# PDM_ROCKPIS_PoE_HAT_FPC.net
KiCad netlist of a schematic drawn in Altium Designer
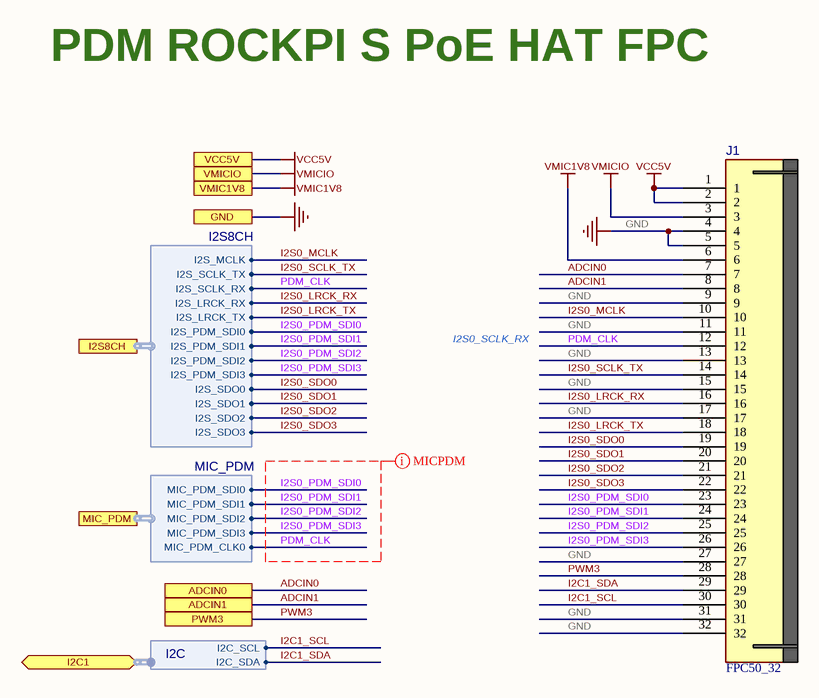
[diagram p0: PDM_ROCKPIS_PoE_HAT_FPC.SchDoc]

(export (version "E")
  (design (tool "Eeschema 10.0.6"))
  (components
    (comp (ref "J1")
      (value "FPC50_32")
      (footprint "FPC50_32D")
      (description "CONN, FPC, 0.50mm pitch, RightAngle, Bot. Contact")
      (fields (field (name "MANF") "OMRON") (field (name "MANF_P#") "XF2M-3215-1A"))
      (libsource (lib "conn_fpc") (part "FPC50_32D"))
    )
  )
  (nets
    (net (code "4") (name "/ADCIN0") (class "Default")
      (node (ref "J1") (pin "7") (pinfunction "7_7") (pintype "passive"))
    )
    (net (code "5") (name "/ADCIN1") (class "Default")
      (node (ref "J1") (pin "8") (pinfunction "8_8") (pintype "passive"))
    )
    (net (code "6") (name "/I2C1_SCL") (class "Default")
      (node (ref "J1") (pin "30") (pinfunction "30_30") (pintype "passive"))
    )
    (net (code "7") (name "/I2C1_SDA") (class "Default")
      (node (ref "J1") (pin "29") (pinfunction "29_29") (pintype "passive"))
    )
    (net (code "8") (name "/I2S0_LRCK_RX") (class "Default")
      (node (ref "J1") (pin "16") (pinfunction "16_16") (pintype "passive"))
    )
    (net (code "9") (name "/I2S0_LRCK_TX") (class "Default")
      (node (ref "J1") (pin "18") (pinfunction "18_18") (pintype "passive"))
    )
    (net (code "10") (name "/I2S0_MCLK") (class "Default")
      (node (ref "J1") (pin "10") (pinfunction "10_10") (pintype "passive"))
    )
    (net (code "11") (name "/I2S0_PDM_SDI0") (class "Default")
      (node (ref "J1") (pin "23") (pinfunction "23_23") (pintype "passive"))
    )
    (net (code "12") (name "/I2S0_PDM_SDI1") (class "Default")
      (node (ref "J1") (pin "24") (pinfunction "24_24") (pintype "passive"))
    )
    (net (code "13") (name "/I2S0_PDM_SDI2") (class "Default")
      (node (ref "J1") (pin "25") (pinfunction "25_25") (pintype "passive"))
    )
    (net (code "14") (name "/I2S0_PDM_SDI3") (class "Default")
      (node (ref "J1") (pin "26") (pinfunction "26_26") (pintype "passive"))
    )
    (net (code "15") (name "/I2S0_SCLK_TX") (class "Default")
      (node (ref "J1") (pin "14") (pinfunction "14_14") (pintype "passive"))
    )
    (net (code "16") (name "/I2S0_SDO0") (class "Default")
      (node (ref "J1") (pin "19") (pinfunction "19_19") (pintype "passive"))
    )
    (net (code "17") (name "/I2S0_SDO1") (class "Default")
      (node (ref "J1") (pin "20") (pinfunction "20_20") (pintype "passive"))
    )
    (net (code "18") (name "/I2S0_SDO2") (class "Default")
      (node (ref "J1") (pin "21") (pinfunction "21_21") (pintype "passive"))
    )
    (net (code "19") (name "/I2S0_SDO3") (class "Default")
      (node (ref "J1") (pin "22") (pinfunction "22_22") (pintype "passive"))
    )
    (net (code "20") (name "/PDM_CLK") (class "Default")
      (node (ref "J1") (pin "12") (pinfunction "12_12") (pintype "passive"))
    )
    (net (code "21") (name "/PWM3") (class "Default")
      (node (ref "J1") (pin "28") (pinfunction "28_28") (pintype "passive"))
    )
    (net (code "25") (name "GND") (class "Default")
      (node (ref "J1") (pin "11") (pinfunction "11_11") (pintype "passive"))
      (node (ref "J1") (pin "13") (pinfunction "13_13") (pintype "passive"))
      (node (ref "J1") (pin "15") (pinfunction "15_15") (pintype "passive"))
      (node (ref "J1") (pin "17") (pinfunction "17_17") (pintype "passive"))
      (node (ref "J1") (pin "27") (pinfunction "27_27") (pintype "passive"))
      (node (ref "J1") (pin "31") (pinfunction "31_31") (pintype "passive"))
      (node (ref "J1") (pin "32") (pinfunction "32_32") (pintype "passive"))
      (node (ref "J1") (pin "4") (pinfunction "4_4") (pintype "passive"))
      (node (ref "J1") (pin "5") (pinfunction "5_5") (pintype "passive"))
      (node (ref "J1") (pin "9") (pinfunction "9_9") (pintype "passive"))
    )
    (net (code "26") (name "VCC5V") (class "Default")
      (node (ref "J1") (pin "1") (pinfunction "1_1") (pintype "passive"))
      (node (ref "J1") (pin "2") (pinfunction "2_2") (pintype "passive"))
    )
    (net (code "27") (name "VMIC1V8") (class "Default")
      (node (ref "J1") (pin "6") (pinfunction "6_6") (pintype "passive"))
    )
    (net (code "28") (name "VMICIO") (class "Default")
      (node (ref "J1") (pin "3") (pinfunction "3_3") (pintype "passive"))
    )
  )
)
